# Sheet2.net
KiCad netlist of a schematic drawn in Altium Designer
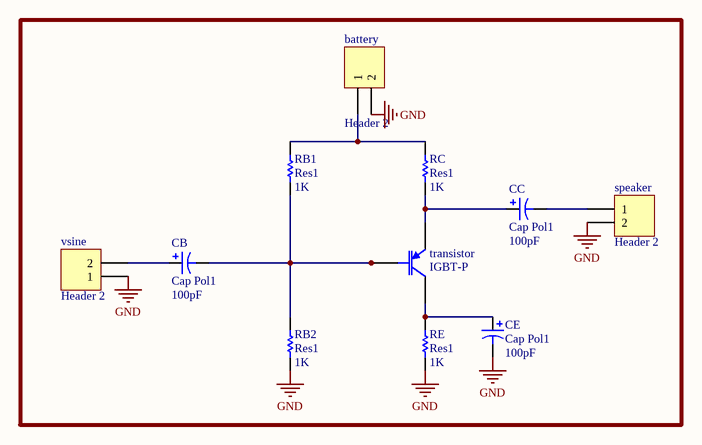
[diagram p0: Sheet2.SchDoc]

(export (version "E")
  (design (tool "Eeschema 10.0.6"))
  (components
    (comp (ref "battery")
      (value "Header 2")
      (footprint "HDR1X2")
      (description "Header, 2-Pin")
      (fields (field (name "PUBLISHER") "Altium Limited"))
      (libsource (lib "") (part "Header 2_2"))
    )
    (comp (ref "CB")
      (value "Cap Pol1")
      (footprint "RB7.6-15")
      (description "Polarized Capacitor (Radial)")
      (fields (field (name "ALTIUM_VALUE") "100pF") (field (name "PUBLISHER") "Altium Limited"))
      (libsource (lib "Miscellaneous Devices") (part "Cap Pol1"))
    )
    (comp (ref "CC")
      (value "Cap Pol1")
      (footprint "RB7.6-15")
      (description "Polarized Capacitor (Radial)")
      (fields (field (name "ALTIUM_VALUE") "100pF") (field (name "PUBLISHER") "Altium Limited"))
      (libsource (lib "Miscellaneous Devices") (part "Cap Pol1"))
    )
    (comp (ref "CE")
      (value "Cap Pol1")
      (footprint "RB7.6-15")
      (description "Polarized Capacitor (Radial)")
      (fields (field (name "ALTIUM_VALUE") "100pF") (field (name "PUBLISHER") "Altium Limited"))
      (libsource (lib "Miscellaneous Devices") (part "Cap Pol1"))
    )
    (comp (ref "RB1")
      (value "Res1")
      (footprint "AXIAL-0.3")
      (description "Resistor")
      (fields (field (name "ALTIUM_VALUE") "1K") (field (name "PUBLISHER") "Altium Limited"))
      (libsource (lib "Miscellaneous Devices") (part "Res1"))
    )
    (comp (ref "RB2")
      (value "Res1")
      (footprint "AXIAL-0.3")
      (description "Resistor")
      (fields (field (name "ALTIUM_VALUE") "1K") (field (name "PUBLISHER") "Altium Limited"))
      (libsource (lib "Miscellaneous Devices") (part "Res1"))
    )
    (comp (ref "RC")
      (value "Res1")
      (footprint "AXIAL-0.3")
      (description "Resistor")
      (fields (field (name "ALTIUM_VALUE") "1K") (field (name "PUBLISHER") "Altium Limited"))
      (libsource (lib "Miscellaneous Devices") (part "Res1"))
    )
    (comp (ref "RE")
      (value "Res1")
      (footprint "AXIAL-0.3")
      (description "Resistor")
      (fields (field (name "ALTIUM_VALUE") "1K") (field (name "PUBLISHER") "Altium Limited"))
      (libsource (lib "Miscellaneous Devices") (part "Res1"))
    )
    (comp (ref "speaker")
      (value "Header 2")
      (footprint "HDR1X2")
      (description "Header, 2-Pin")
      (fields (field (name "PUBLISHER") "Altium Limited"))
      (libsource (lib "Miscellaneous Connectors") (part "Header 2"))
    )
    (comp (ref "transistor")
      (value "IGBT-P")
      (footprint "TO-264-AA")
      (description "PNP Bipolar Junction Transistor")
      (fields (field (name "PUBLISHER") "Altium Limited"))
      (libsource (lib "Miscellaneous Devices") (part "IGBT-P"))
    )
    (comp (ref "vsine")
      (value "Header 2")
      (footprint "HDR1X2")
      (description "Header, 2-Pin")
      (fields (field (name "PUBLISHER") "Altium Limited"))
      (libsource (lib "") (part "Header 2_1"))
    )
  )
  (nets
    (net (code "1") (name "GND") (class "Default")
      (node (ref "CE") (pin "2") (pinfunction "2_2") (pintype "passive"))
      (node (ref "RB2") (pin "1") (pinfunction "1_1") (pintype "passive"))
      (node (ref "RE") (pin "1") (pinfunction "1_1") (pintype "passive"))
      (node (ref "battery") (pin "2") (pinfunction "2_2") (pintype "passive"))
      (node (ref "speaker") (pin "2") (pinfunction "2_2") (pintype "passive"))
      (node (ref "vsine") (pin "1") (pinfunction "1_1") (pintype "passive"))
    )
    (net (code "2") (name "Net-(CB-Pad1)") (class "Default")
      (node (ref "CB") (pin "1") (pinfunction "1_1") (pintype "passive"))
      (node (ref "vsine") (pin "2") (pinfunction "2_2") (pintype "passive"))
    )
    (net (code "3") (name "Net-(CC-Pad2)") (class "Default")
      (node (ref "CC") (pin "2") (pinfunction "2_2") (pintype "passive"))
      (node (ref "speaker") (pin "1") (pinfunction "1_1") (pintype "passive"))
    )
    (net (code "4") (name "Net-(RB1-Pad2)") (class "Default")
      (node (ref "RB1") (pin "2") (pinfunction "2_2") (pintype "passive"))
      (node (ref "RC") (pin "2") (pinfunction "2_2") (pintype "passive"))
      (node (ref "battery") (pin "1") (pinfunction "1_1") (pintype "passive"))
    )
    (net (code "5") (name "Net-(transistor-C)") (class "Default")
      (node (ref "CE") (pin "1") (pinfunction "1_1") (pintype "passive"))
      (node (ref "RE") (pin "2") (pinfunction "2_2") (pintype "passive"))
      (node (ref "transistor") (pin "1") (pinfunction "C_1") (pintype "passive"))
    )
    (net (code "6") (name "Net-(transistor-E)") (class "Default")
      (node (ref "CC") (pin "1") (pinfunction "1_1") (pintype "passive"))
      (node (ref "RC") (pin "1") (pinfunction "1_1") (pintype "passive"))
      (node (ref "transistor") (pin "3") (pinfunction "E_3") (pintype "passive"))
    )
    (net (code "7") (name "Net-(transistor-G)") (class "Default")
      (node (ref "CB") (pin "2") (pinfunction "2_2") (pintype "passive"))
      (node (ref "RB1") (pin "1") (pinfunction "1_1") (pintype "passive"))
      (node (ref "RB2") (pin "2") (pinfunction "2_2") (pintype "passive"))
      (node (ref "transistor") (pin "2") (pinfunction "G_2") (pintype "passive"))
    )
  )
)
